# Sheet2.net
KiCad netlist of a schematic drawn in Altium Designer
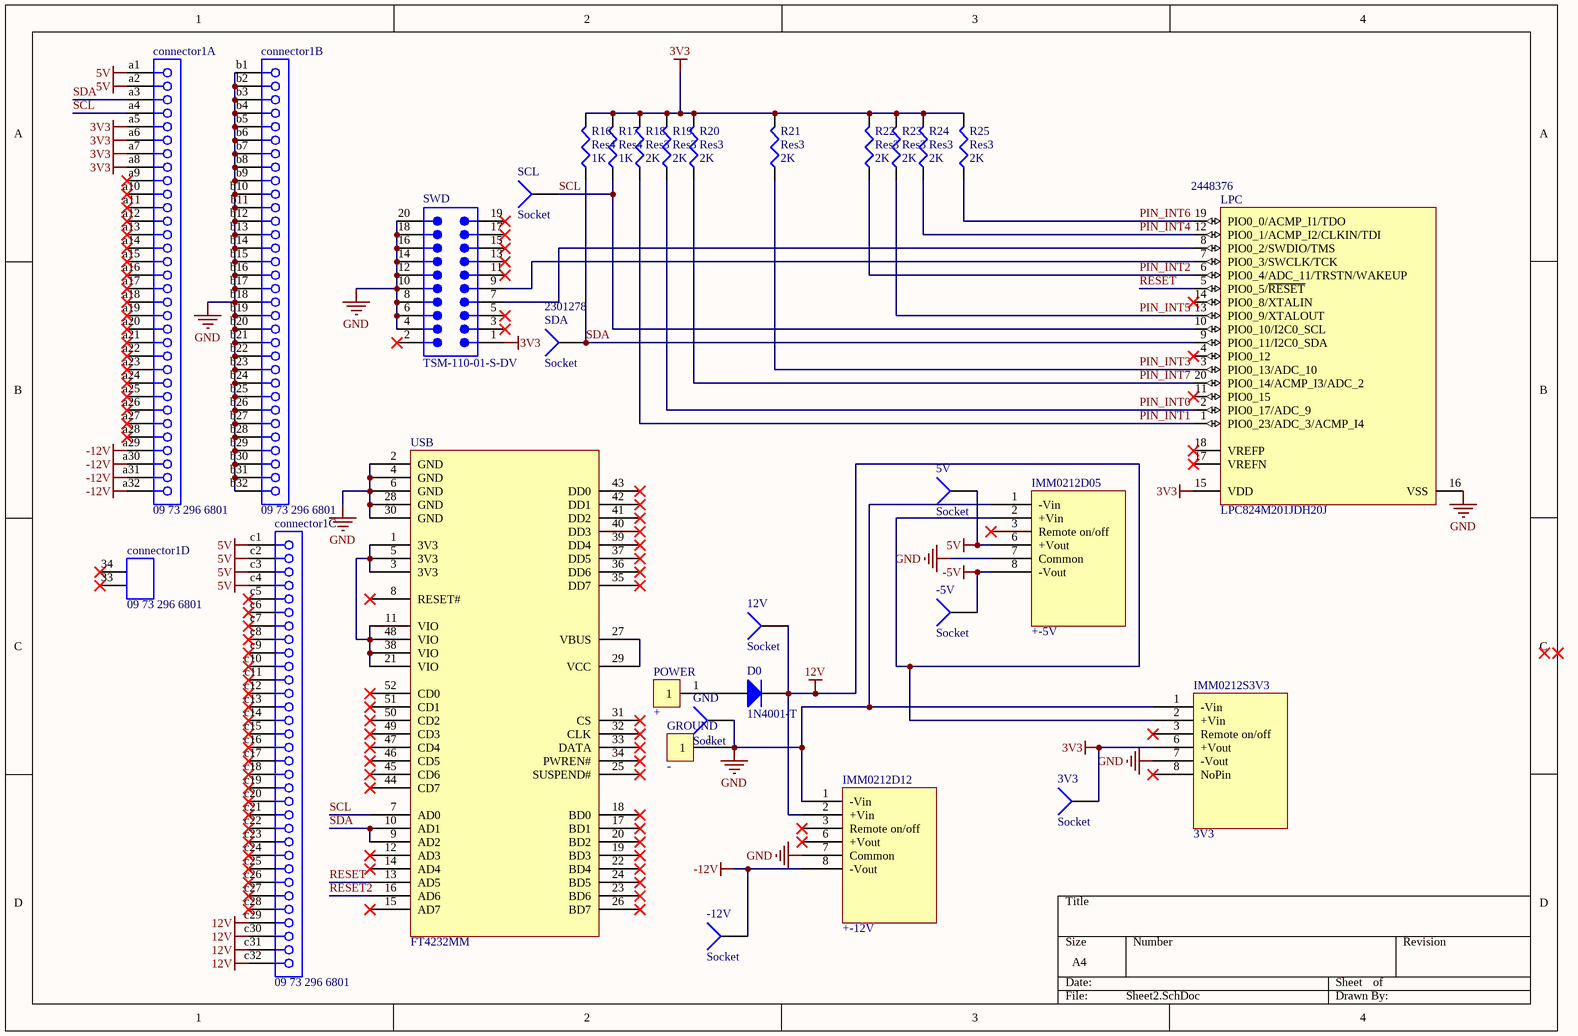
[diagram p0: Sheet2.SchDoc]

(export (version "E")
  (design (tool "Eeschema 10.0.6"))
  (components
    (comp (ref "-5V")
      (value "Socket")
      (footprint "CON1")
      (fields (field (name "PUBLISHER") "Altium Limited"))
      (libsource (lib "Miscellaneous Connectors") (part "Socket"))
    )
    (comp (ref "-12V")
      (value "Socket")
      (footprint "CON1")
      (fields (field (name "PUBLISHER") "Altium Limited"))
      (libsource (lib "Miscellaneous Connectors") (part "Socket"))
    )
    (comp (ref "3V3")
      (value "Socket")
      (footprint "CON1")
      (fields (field (name "PUBLISHER") "Altium Limited"))
      (libsource (lib "Miscellaneous Connectors") (part "Socket"))
    )
    (comp (ref "5V")
      (value "Socket")
      (footprint "CON1")
      (fields (field (name "PUBLISHER") "Altium Limited"))
      (libsource (lib "Miscellaneous Connectors") (part "Socket"))
    )
    (comp (ref "12V")
      (value "Socket")
      (footprint "CON1")
      (fields (field (name "PUBLISHER") "Altium Limited"))
      (libsource (lib "Miscellaneous Connectors") (part "Socket"))
    )
    (comp (ref "connector1")
      (value "09 73 296 6801")
      (footprint "DAC testerPCB:0973296X801")
      (fields (field (name "PUBLISHER") "Altium Limited"))
      (libsource (lib "HARTING DIN 41612 Type R") (part "09 73 296 6801"))
    )
    (comp (ref "D0")
      (value "1N4001-T")
      (footprint "DIOD-DO-41-P-2_V")
      (description "1.0 A Rectifier, 15 pF, 50 V, -65 to 150 degC, 2-Pin DO-41 Plastic, RoHS, Tape and Reel")
      (fields (field (name "MANUFACTURER") "Diodes Inc"))
      (libsource (lib "Altium Content Vault") (part "CMP-0639-00006-2"))
    )
    (comp (ref "GND")
      (value "Socket")
      (footprint "CON1")
      (fields (field (name "PUBLISHER") "Altium Limited"))
      (libsource (lib "Miscellaneous Connectors") (part "Socket"))
    )
    (comp (ref "GROUND") (value "-") (footprint "RA") (libsource (lib "schlib") (part "Power")))
    (comp (ref "IMM0212D05")
      (value "+-5V")
      (footprint "my_pcb:SIP8")
      (libsource (lib "schlib") (part "IMM0212D05"))
    )
    (comp (ref "IMM0212D12")
      (value "+-12V")
      (footprint "SIP8")
      (libsource (lib "schlib") (part "IMM0212D05"))
    )
    (comp (ref "IMM0212S3V3")
      (value "3V3")
      (footprint "my_pcb:SIP8")
      (libsource (lib "schlib") (part "Component_1"))
    )
    (comp (ref "LPC")
      (value "LPC824M201JDH20J")
      (footprint "NXP-SOT360-1_N")
      (fields
        (field (name "MANUFACTURER") "NXP Semiconductors")
        (field (name "PARTNUMBER") "LPC824M201JDH20")
        (field (name "SUPPLIER PART NUMBER 1") "2448376")
      )
      (libsource (lib "Altium Content Vault") (part "CMP-0173-00095-1"))
    )
    (comp (ref "POWER") (value "+") (footprint "RA") (libsource (lib "schlib") (part "Power")))
    (comp (ref "R16")
      (value "Res4")
      (footprint "J1-0603")
      (description "Resistor")
      (fields (field (name "ALTIUM_VALUE") "1K") (field (name "PUBLISHER") "Altium Limited"))
      (libsource (lib "Miscellaneous Devices") (part "Res3"))
    )
    (comp (ref "R17")
      (value "Res4")
      (footprint "J1-0603")
      (description "Resistor")
      (fields (field (name "ALTIUM_VALUE") "1K") (field (name "PUBLISHER") "Altium Limited"))
      (libsource (lib "Miscellaneous Devices") (part "Res3"))
    )
    (comp (ref "R18")
      (value "Res3")
      (footprint "J1-0603")
      (description "Resistor")
      (fields (field (name "ALTIUM_VALUE") "2K") (field (name "PUBLISHER") "Altium Limited"))
      (libsource (lib "Miscellaneous Devices") (part "Res3"))
    )
    (comp (ref "R19")
      (value "Res3")
      (footprint "J1-0603")
      (description "Resistor")
      (fields (field (name "ALTIUM_VALUE") "2K") (field (name "PUBLISHER") "Altium Limited"))
      (libsource (lib "Miscellaneous Devices") (part "Res3"))
    )
    (comp (ref "R20")
      (value "Res3")
      (footprint "J1-0603")
      (description "Resistor")
      (fields (field (name "ALTIUM_VALUE") "2K") (field (name "PUBLISHER") "Altium Limited"))
      (libsource (lib "Miscellaneous Devices") (part "Res3"))
    )
    (comp (ref "R21")
      (value "Res3")
      (footprint "J1-0603")
      (description "Resistor")
      (fields (field (name "ALTIUM_VALUE") "2K") (field (name "PUBLISHER") "Altium Limited"))
      (libsource (lib "Miscellaneous Devices") (part "Res3"))
    )
    (comp (ref "R22")
      (value "Res3")
      (footprint "J1-0603")
      (description "Resistor")
      (fields (field (name "ALTIUM_VALUE") "2K") (field (name "PUBLISHER") "Altium Limited"))
      (libsource (lib "Miscellaneous Devices") (part "Res3"))
    )
    (comp (ref "R23")
      (value "Res3")
      (footprint "J1-0603")
      (description "Resistor")
      (fields (field (name "ALTIUM_VALUE") "2K") (field (name "PUBLISHER") "Altium Limited"))
      (libsource (lib "Miscellaneous Devices") (part "Res3"))
    )
    (comp (ref "R24")
      (value "Res3")
      (footprint "J1-0603")
      (description "Resistor")
      (fields (field (name "ALTIUM_VALUE") "2K") (field (name "PUBLISHER") "Altium Limited"))
      (libsource (lib "Miscellaneous Devices") (part "Res3"))
    )
    (comp (ref "R25")
      (value "Res3")
      (footprint "J1-0603")
      (description "Resistor")
      (fields (field (name "ALTIUM_VALUE") "2K") (field (name "PUBLISHER") "Altium Limited"))
      (libsource (lib "Miscellaneous Devices") (part "Res3"))
    )
    (comp (ref "SCL")
      (value "Socket")
      (footprint "CON1")
      (fields (field (name "PUBLISHER") "Altium Limited"))
      (libsource (lib "Miscellaneous Connectors") (part "Socket"))
    )
    (comp (ref "SDA")
      (value "Socket")
      (footprint "CON1")
      (fields (field (name "SUPPLIER PART NUMBER 1") "2301278") (field (name "PUBLISHER") "Altium Limited"))
      (libsource (lib "Miscellaneous Connectors") (part "Socket"))
    )
    (comp (ref "SWD")
      (value "TSM-110-01-S-DV")
      (footprint "SMTC-TSM-110-01-X-DV")
      (fields (field (name "MANUFACTURER") "Samtec"))
      (libsource (lib "Altium Content Vault") (part "CMP-1024-00283-1"))
    )
    (comp (ref "USB")
      (value "FT4232MM")
      (footprint "ICfootprint3:FT4232MM")
      (description "FDTI mini module")
      (libsource (lib "nxp_device") (part "FT4232MM"))
    )
  )
  (nets
    (net (code "1") (name "-5V") (class "Default")
      (node (ref "-5V") (pin "1") (pinfunction "1_1") (pintype "passive"))
      (node (ref "IMM0212D05") (pin "8") (pinfunction "-Vout_8") (pintype "passive"))
    )
    (net (code "2") (name "-12V") (class "Default")
      (node (ref "-12V") (pin "1") (pinfunction "1_1") (pintype "passive"))
      (node (ref "IMM0212D12") (pin "8") (pinfunction "-Vout_8") (pintype "passive"))
      (node (ref "connector1") (pin "a29") (pinfunction "a29_a29") (pintype "passive"))
      (node (ref "connector1") (pin "a30") (pinfunction "a30_a30") (pintype "passive"))
      (node (ref "connector1") (pin "a31") (pinfunction "a31_a31") (pintype "passive"))
      (node (ref "connector1") (pin "a32") (pinfunction "a32_a32") (pintype "passive"))
    )
    (net (code "3") (name "/PIN_INT0") (class "Default")
      (node (ref "LPC") (pin "2") (pinfunction "PIO0_17/ADC_9_2") (pintype "bidirectional"))
      (node (ref "R19") (pin "1") (pinfunction "1_1") (pintype "passive"))
    )
    (net (code "4") (name "/PIN_INT1") (class "Default")
      (node (ref "LPC") (pin "1") (pinfunction "PIO0_23/ADC_3/ACMP_I4_1") (pintype "bidirectional"))
      (node (ref "R18") (pin "1") (pinfunction "1_1") (pintype "passive"))
    )
    (net (code "5") (name "/PIN_INT2") (class "Default")
      (node (ref "LPC") (pin "6") (pinfunction "PIO0_4/ADC_11/TRSTN/WAKEUP_6") (pintype "bidirectional"))
      (node (ref "R22") (pin "1") (pinfunction "1_1") (pintype "passive"))
    )
    (net (code "6") (name "/PIN_INT3") (class "Default")
      (node (ref "LPC") (pin "3") (pinfunction "PIO0_13/ADC_10_3") (pintype "bidirectional"))
      (node (ref "R21") (pin "1") (pinfunction "1_1") (pintype "passive"))
    )
    (net (code "7") (name "/PIN_INT4") (class "Default")
      (node (ref "LPC") (pin "12") (pinfunction "PIO0_1/ACMP_I2/CLKIN/TDI_12") (pintype "bidirectional"))
      (node (ref "R24") (pin "1") (pinfunction "1_1") (pintype "passive"))
    )
    (net (code "8") (name "/PIN_INT5") (class "Default")
      (node (ref "LPC") (pin "13") (pinfunction "PIO0_9/XTALOUT_13") (pintype "bidirectional"))
      (node (ref "R23") (pin "1") (pinfunction "1_1") (pintype "passive"))
    )
    (net (code "9") (name "/PIN_INT6") (class "Default")
      (node (ref "LPC") (pin "19") (pinfunction "PIO0_0/ACMP_I1/TDO_19") (pintype "bidirectional"))
      (node (ref "R25") (pin "1") (pinfunction "1_1") (pintype "passive"))
    )
    (net (code "10") (name "/PIN_INT7") (class "Default")
      (node (ref "LPC") (pin "20") (pinfunction "PIO0_14/ACMP_I3/ADC_2_20") (pintype "bidirectional"))
      (node (ref "R20") (pin "1") (pinfunction "1_1") (pintype "passive"))
    )
    (net (code "11") (name "/RESET") (class "Default")
      (node (ref "LPC") (pin "5") (pinfunction "PIO0_5/~{RESET}_5") (pintype "bidirectional"))
      (node (ref "USB") (pin "13") (pinfunction "AD5_13") (pintype "passive"))
    )
    (net (code "12") (name "/RESET2") (class "Default")
      (node (ref "USB") (pin "16") (pinfunction "AD6_16") (pintype "passive"))
    )
    (net (code "13") (name "/SCL") (class "Default")
      (node (ref "LPC") (pin "10") (pinfunction "PIO0_10/I2C0_SCL_10") (pintype "bidirectional"))
      (node (ref "R17") (pin "1") (pinfunction "1_1") (pintype "passive"))
      (node (ref "SCL") (pin "1") (pinfunction "1_1") (pintype "passive"))
      (node (ref "USB") (pin "7") (pinfunction "AD0_7") (pintype "passive"))
      (node (ref "connector1") (pin "a4") (pinfunction "a4_a4") (pintype "passive"))
    )
    (net (code "14") (name "/SDA") (class "Default")
      (node (ref "LPC") (pin "9") (pinfunction "PIO0_11/I2C0_SDA_9") (pintype "bidirectional"))
      (node (ref "R16") (pin "1") (pinfunction "1_1") (pintype "passive"))
      (node (ref "SDA") (pin "1") (pinfunction "1_1") (pintype "passive"))
      (node (ref "USB") (pin "10") (pinfunction "AD1_10") (pintype "passive"))
      (node (ref "USB") (pin "9") (pinfunction "AD2_9") (pintype "passive"))
      (node (ref "connector1") (pin "a3") (pinfunction "a3_a3") (pintype "passive"))
    )
    (net (code "15") (name "3V3") (class "Default")
      (node (ref "3V3") (pin "1") (pinfunction "1_1") (pintype "passive"))
      (node (ref "IMM0212S3V3") (pin "6") (pinfunction "+Vout_6") (pintype "passive"))
      (node (ref "LPC") (pin "15") (pinfunction "VDD_15") (pintype "power_in"))
      (node (ref "R16") (pin "2") (pinfunction "2_2") (pintype "passive"))
      (node (ref "R17") (pin "2") (pinfunction "2_2") (pintype "passive"))
      (node (ref "R18") (pin "2") (pinfunction "2_2") (pintype "passive"))
      (node (ref "R19") (pin "2") (pinfunction "2_2") (pintype "passive"))
      (node (ref "R20") (pin "2") (pinfunction "2_2") (pintype "passive"))
      (node (ref "R21") (pin "2") (pinfunction "2_2") (pintype "passive"))
      (node (ref "R22") (pin "2") (pinfunction "2_2") (pintype "passive"))
      (node (ref "R23") (pin "2") (pinfunction "2_2") (pintype "passive"))
      (node (ref "R24") (pin "2") (pinfunction "2_2") (pintype "passive"))
      (node (ref "R25") (pin "2") (pinfunction "2_2") (pintype "passive"))
      (node (ref "SWD") (pin "1") (pinfunction "1_1") (pintype "passive"))
      (node (ref "connector1") (pin "a5") (pinfunction "a5_a5") (pintype "passive"))
      (node (ref "connector1") (pin "a6") (pinfunction "a6_a6") (pintype "passive"))
      (node (ref "connector1") (pin "a7") (pinfunction "a7_a7") (pintype "passive"))
      (node (ref "connector1") (pin "a8") (pinfunction "a8_a8") (pintype "passive"))
    )
    (net (code "16") (name "5V") (class "Default")
      (node (ref "5V") (pin "1") (pinfunction "1_1") (pintype "passive"))
      (node (ref "IMM0212D05") (pin "6") (pinfunction "+Vout_6") (pintype "passive"))
      (node (ref "connector1") (pin "a1") (pinfunction "a1_a1") (pintype "passive"))
      (node (ref "connector1") (pin "a2") (pinfunction "a2_a2") (pintype "passive"))
      (node (ref "connector1") (pin "c1") (pinfunction "c1_c1") (pintype "passive"))
      (node (ref "connector1") (pin "c2") (pinfunction "c2_c2") (pintype "passive"))
      (node (ref "connector1") (pin "c3") (pinfunction "c3_c3") (pintype "passive"))
      (node (ref "connector1") (pin "c4") (pinfunction "c4_c4") (pintype "passive"))
    )
    (net (code "17") (name "12V") (class "Default")
      (node (ref "12V") (pin "1") (pinfunction "1_1") (pintype "passive"))
      (node (ref "D0") (pin "2") (pinfunction "K_2") (pintype "passive"))
      (node (ref "IMM0212D05") (pin "2") (pinfunction "+Vin_2") (pintype "passive"))
      (node (ref "IMM0212D12") (pin "2") (pinfunction "+Vin_2") (pintype "passive"))
      (node (ref "IMM0212S3V3") (pin "2") (pinfunction "+Vin_2") (pintype "passive"))
      (node (ref "connector1") (pin "c29") (pinfunction "c29_c29") (pintype "passive"))
      (node (ref "connector1") (pin "c30") (pinfunction "c30_c30") (pintype "passive"))
      (node (ref "connector1") (pin "c31") (pinfunction "c31_c31") (pintype "passive"))
      (node (ref "connector1") (pin "c32") (pinfunction "c32_c32") (pintype "passive"))
    )
    (net (code "18") (name "GND") (class "Default")
      (node (ref "GND") (pin "1") (pinfunction "1_1") (pintype "passive"))
      (node (ref "GROUND") (pin "1") (pinfunction "1_1") (pintype "passive"))
      (node (ref "IMM0212D05") (pin "1") (pinfunction "-Vin_1") (pintype "passive"))
      (node (ref "IMM0212D05") (pin "7") (pinfunction "Common_7") (pintype "passive"))
      (node (ref "IMM0212D12") (pin "1") (pinfunction "-Vin_1") (pintype "passive"))
      (node (ref "IMM0212D12") (pin "7") (pinfunction "Common_7") (pintype "passive"))
      (node (ref "IMM0212S3V3") (pin "1") (pinfunction "-Vin_1") (pintype "passive"))
      (node (ref "IMM0212S3V3") (pin "7") (pinfunction "-Vout_7") (pintype "passive"))
      (node (ref "LPC") (pin "16") (pinfunction "VSS_16") (pintype "power_in"))
      (node (ref "SWD") (pin "10") (pinfunction "10_10") (pintype "passive"))
      (node (ref "SWD") (pin "12") (pinfunction "12_12") (pintype "passive"))
      (node (ref "SWD") (pin "14") (pinfunction "14_14") (pintype "passive"))
      (node (ref "SWD") (pin "16") (pinfunction "16_16") (pintype "passive"))
      (node (ref "SWD") (pin "18") (pinfunction "18_18") (pintype "passive"))
      (node (ref "SWD") (pin "20") (pinfunction "20_20") (pintype "passive"))
      (node (ref "SWD") (pin "4") (pinfunction "4_4") (pintype "passive"))
      (node (ref "SWD") (pin "6") (pinfunction "6_6") (pintype "passive"))
      (node (ref "SWD") (pin "8") (pinfunction "8_8") (pintype "passive"))
      (node (ref "USB") (pin "2") (pinfunction "GND_2") (pintype "passive"))
      (node (ref "USB") (pin "28") (pinfunction "GND_28") (pintype "passive"))
      (node (ref "USB") (pin "30") (pinfunction "GND_30") (pintype "passive"))
      (node (ref "USB") (pin "4") (pinfunction "GND_4") (pintype "passive"))
      (node (ref "USB") (pin "6") (pinfunction "GND_6") (pintype "passive"))
      (node (ref "connector1") (pin "b1") (pinfunction "b1_b1") (pintype "passive"))
      (node (ref "connector1") (pin "b10") (pinfunction "b10_b10") (pintype "passive"))
      (node (ref "connector1") (pin "b11") (pinfunction "b11_b11") (pintype "passive"))
      (node (ref "connector1") (pin "b12") (pinfunction "b12_b12") (pintype "passive"))
      (node (ref "connector1") (pin "b13") (pinfunction "b13_b13") (pintype "passive"))
      (node (ref "connector1") (pin "b14") (pinfunction "b14_b14") (pintype "passive"))
      (node (ref "connector1") (pin "b15") (pinfunction "b15_b15") (pintype "passive"))
      (node (ref "connector1") (pin "b16") (pinfunction "b16_b16") (pintype "passive"))
      (node (ref "connector1") (pin "b17") (pinfunction "b17_b17") (pintype "passive"))
      (node (ref "connector1") (pin "b18") (pinfunction "b18_b18") (pintype "passive"))
      (node (ref "connector1") (pin "b19") (pinfunction "b19_b19") (pintype "passive"))
      (node (ref "connector1") (pin "b2") (pinfunction "b2_b2") (pintype "passive"))
      (node (ref "connector1") (pin "b20") (pinfunction "b20_b20") (pintype "passive"))
      (node (ref "connector1") (pin "b21") (pinfunction "b21_b21") (pintype "passive"))
      (node (ref "connector1") (pin "b22") (pinfunction "b22_b22") (pintype "passive"))
      (node (ref "connector1") (pin "b23") (pinfunction "b23_b23") (pintype "passive"))
      (node (ref "connector1") (pin "b24") (pinfunction "b24_b24") (pintype "passive"))
      (node (ref "connector1") (pin "b25") (pinfunction "b25_b25") (pintype "passive"))
      (node (ref "connector1") (pin "b26") (pinfunction "b26_b26") (pintype "passive"))
      (node (ref "connector1") (pin "b27") (pinfunction "b27_b27") (pintype "passive"))
      (node (ref "connector1") (pin "b28") (pinfunction "b28_b28") (pintype "passive"))
      (node (ref "connector1") (pin "b29") (pinfunction "b29_b29") (pintype "passive"))
      (node (ref "connector1") (pin "b3") (pinfunction "b3_b3") (pintype "passive"))
      (node (ref "connector1") (pin "b30") (pinfunction "b30_b30") (pintype "passive"))
      (node (ref "connector1") (pin "b31") (pinfunction "b31_b31") (pintype "passive"))
      (node (ref "connector1") (pin "b32") (pinfunction "b32_b32") (pintype "passive"))
      (node (ref "connector1") (pin "b4") (pinfunction "b4_b4") (pintype "passive"))
      (node (ref "connector1") (pin "b5") (pinfunction "b5_b5") (pintype "passive"))
      (node (ref "connector1") (pin "b6") (pinfunction "b6_b6") (pintype "passive"))
      (node (ref "connector1") (pin "b7") (pinfunction "b7_b7") (pintype "passive"))
      (node (ref "connector1") (pin "b8") (pinfunction "b8_b8") (pintype "passive"))
      (node (ref "connector1") (pin "b9") (pinfunction "b9_b9") (pintype "passive"))
    )
    (net (code "19") (name "Net-(D0-A)") (class "Default")
      (node (ref "D0") (pin "1") (pinfunction "A_1") (pintype "passive"))
      (node (ref "POWER") (pin "1") (pinfunction "1_1") (pintype "passive"))
    )
    (net (code "20") (name "Net-(LPC-PIO0_2{slash}SWDIO{slash}TMS)") (class "Default")
      (node (ref "LPC") (pin "8") (pinfunction "PIO0_2/SWDIO/TMS_8") (pintype "bidirectional"))
      (node (ref "SWD") (pin "7") (pinfunction "7_7") (pintype "passive"))
    )
    (net (code "21") (name "Net-(LPC-PIO0_3{slash}SWCLK{slash}TCK)") (class "Default")
      (node (ref "LPC") (pin "7") (pinfunction "PIO0_3/SWCLK/TCK_7") (pintype "bidirectional"))
      (node (ref "SWD") (pin "9") (pinfunction "9_9") (pintype "passive"))
    )
    (net (code "22") (name "Net-(USB-3V3-Pad1)") (class "Default")
      (node (ref "USB") (pin "1") (pinfunction "3V3_1") (pintype "passive"))
      (node (ref "USB") (pin "11") (pinfunction "VIO_11") (pintype "passive"))
      (node (ref "USB") (pin "21") (pinfunction "VIO_21") (pintype "passive"))
      (node (ref "USB") (pin "3") (pinfunction "3V3_3") (pintype "passive"))
      (node (ref "USB") (pin "38") (pinfunction "VIO_38") (pintype "passive"))
      (node (ref "USB") (pin "48") (pinfunction "VIO_48") (pintype "passive"))
      (node (ref "USB") (pin "5") (pinfunction "3V3_5") (pintype "passive"))
    )
    (net (code "23") (name "Net-(USB-VBUS)") (class "Default")
      (node (ref "USB") (pin "27") (pinfunction "VBUS_27") (pintype "passive"))
      (node (ref "USB") (pin "29") (pinfunction "VCC_29") (pintype "passive"))
    )
    (net (code "24") (name "unconnected-(IMM0212D05-Remote_on{slash}off-Pad3)") (class "Default")
      (node (ref "IMM0212D05") (pin "3") (pinfunction "Remote_on/off_3") (pintype "passive+no_connect"))
    )
    (net (code "25") (name "unconnected-(IMM0212D12-+Vout-Pad6)") (class "Default")
      (node (ref "IMM0212D12") (pin "6") (pinfunction "+Vout_6") (pintype "passive+no_connect"))
    )
    (net (code "26") (name "unconnected-(IMM0212D12-Remote_on{slash}off-Pad3)") (class "Default")
      (node (ref "IMM0212D12") (pin "3") (pinfunction "Remote_on/off_3") (pintype "passive+no_connect"))
    )
    (net (code "27") (name "unconnected-(IMM0212S3V3-NoPin-Pad8)") (class "Default")
      (node (ref "IMM0212S3V3") (pin "8") (pinfunction "NoPin_8") (pintype "passive+no_connect"))
    )
    (net (code "28") (name "unconnected-(IMM0212S3V3-Remote_on{slash}off-Pad3)") (class "Default")
      (node (ref "IMM0212S3V3") (pin "3") (pinfunction "Remote_on/off_3") (pintype "passive+no_connect"))
    )
    (net (code "29") (name "unconnected-(LPC-PIO0_8{slash}XTALIN-Pad14)") (class "Default")
      (node (ref "LPC") (pin "14") (pinfunction "PIO0_8/XTALIN_14") (pintype "bidirectional+no_connect"))
    )
    (net (code "30") (name "unconnected-(LPC-PIO0_12-Pad4)") (class "Default")
      (node (ref "LPC") (pin "4") (pinfunction "PIO0_12_4") (pintype "bidirectional+no_connect"))
    )
    (net (code "31") (name "unconnected-(LPC-PIO0_15-Pad11)") (class "Default")
      (node (ref "LPC") (pin "11") (pinfunction "PIO0_15_11") (pintype "bidirectional+no_connect"))
    )
    (net (code "32") (name "unconnected-(LPC-VREFN-Pad17)") (class "Default")
      (node (ref "LPC") (pin "17") (pinfunction "VREFN_17") (pintype "power_in+no_connect"))
    )
    (net (code "33") (name "unconnected-(LPC-VREFP-Pad18)") (class "Default")
      (node (ref "LPC") (pin "18") (pinfunction "VREFP_18") (pintype "power_in+no_connect"))
    )
    (net (code "34") (name "unconnected-(SWD-Pad2)") (class "Default")
      (node (ref "SWD") (pin "2") (pinfunction "2_2") (pintype "passive+no_connect"))
    )
    (net (code "35") (name "unconnected-(SWD-Pad3)") (class "Default")
      (node (ref "SWD") (pin "3") (pinfunction "3_3") (pintype "passive+no_connect"))
    )
    (net (code "36") (name "unconnected-(SWD-Pad5)") (class "Default")
      (node (ref "SWD") (pin "5") (pinfunction "5_5") (pintype "passive+no_connect"))
    )
    (net (code "37") (name "unconnected-(SWD-Pad11)") (class "Default")
      (node (ref "SWD") (pin "11") (pinfunction "11_11") (pintype "passive+no_connect"))
    )
    (net (code "38") (name "unconnected-(SWD-Pad13)") (class "Default")
      (node (ref "SWD") (pin "13") (pinfunction "13_13") (pintype "passive+no_connect"))
    )
    (net (code "39") (name "unconnected-(SWD-Pad15)") (class "Default")
      (node (ref "SWD") (pin "15") (pinfunction "15_15") (pintype "passive+no_connect"))
    )
    (net (code "40") (name "unconnected-(SWD-Pad17)") (class "Default")
      (node (ref "SWD") (pin "17") (pinfunction "17_17") (pintype "passive+no_connect"))
    )
    (net (code "41") (name "unconnected-(SWD-Pad19)") (class "Default")
      (node (ref "SWD") (pin "19") (pinfunction "19_19") (pintype "passive+no_connect"))
    )
    (net (code "42") (name "unconnected-(USB-AD3-Pad12)") (class "Default")
      (node (ref "USB") (pin "12") (pinfunction "AD3_12") (pintype "passive+no_connect"))
    )
    (net (code "43") (name "unconnected-(USB-AD4-Pad14)") (class "Default")
      (node (ref "USB") (pin "14") (pinfunction "AD4_14") (pintype "passive+no_connect"))
    )
    (net (code "44") (name "unconnected-(USB-AD7-Pad15)") (class "Default")
      (node (ref "USB") (pin "15") (pinfunction "AD7_15") (pintype "passive+no_connect"))
    )
    (net (code "45") (name "unconnected-(USB-BD0-Pad18)") (class "Default")
      (node (ref "USB") (pin "18") (pinfunction "BD0_18") (pintype "passive+no_connect"))
    )
    (net (code "46") (name "unconnected-(USB-BD1-Pad17)") (class "Default")
      (node (ref "USB") (pin "17") (pinfunction "BD1_17") (pintype "passive+no_connect"))
    )
    (net (code "47") (name "unconnected-(USB-BD2-Pad20)") (class "Default")
      (node (ref "USB") (pin "20") (pinfunction "BD2_20") (pintype "passive+no_connect"))
    )
    (net (code "48") (name "unconnected-(USB-BD3-Pad19)") (class "Default")
      (node (ref "USB") (pin "19") (pinfunction "BD3_19") (pintype "passive+no_connect"))
    )
    (net (code "49") (name "unconnected-(USB-BD4-Pad22)") (class "Default")
      (node (ref "USB") (pin "22") (pinfunction "BD4_22") (pintype "passive+no_connect"))
    )
    (net (code "50") (name "unconnected-(USB-BD5-Pad24)") (class "Default")
      (node (ref "USB") (pin "24") (pinfunction "BD5_24") (pintype "passive+no_connect"))
    )
    (net (code "51") (name "unconnected-(USB-BD6-Pad23)") (class "Default")
      (node (ref "USB") (pin "23") (pinfunction "BD6_23") (pintype "passive+no_connect"))
    )
    (net (code "52") (name "unconnected-(USB-BD7-Pad26)") (class "Default")
      (node (ref "USB") (pin "26") (pinfunction "BD7_26") (pintype "passive+no_connect"))
    )
    (net (code "53") (name "unconnected-(USB-CD0-Pad52)") (class "Default")
      (node (ref "USB") (pin "52") (pinfunction "CD0_52") (pintype "passive+no_connect"))
    )
    (net (code "54") (name "unconnected-(USB-CD1-Pad51)") (class "Default")
      (node (ref "USB") (pin "51") (pinfunction "CD1_51") (pintype "passive+no_connect"))
    )
    (net (code "55") (name "unconnected-(USB-CD2-Pad50)") (class "Default")
      (node (ref "USB") (pin "50") (pinfunction "CD2_50") (pintype "passive+no_connect"))
    )
    (net (code "56") (name "unconnected-(USB-CD3-Pad49)") (class "Default")
      (node (ref "USB") (pin "49") (pinfunction "CD3_49") (pintype "passive+no_connect"))
    )
    (net (code "57") (name "unconnected-(USB-CD4-Pad47)") (class "Default")
      (node (ref "USB") (pin "47") (pinfunction "CD4_47") (pintype "passive+no_connect"))
    )
    (net (code "58") (name "unconnected-(USB-CD5-Pad46)") (class "Default")
      (node (ref "USB") (pin "46") (pinfunction "CD5_46") (pintype "passive+no_connect"))
    )
    (net (code "59") (name "unconnected-(USB-CD6-Pad45)") (class "Default")
      (node (ref "USB") (pin "45") (pinfunction "CD6_45") (pintype "passive+no_connect"))
    )
    (net (code "60") (name "unconnected-(USB-CD7-Pad44)") (class "Default")
      (node (ref "USB") (pin "44") (pinfunction "CD7_44") (pintype "passive+no_connect"))
    )
    (net (code "61") (name "unconnected-(USB-CLK-Pad32)") (class "Default")
      (node (ref "USB") (pin "32") (pinfunction "CLK_32") (pintype "passive+no_connect"))
    )
    (net (code "62") (name "unconnected-(USB-CS-Pad31)") (class "Default")
      (node (ref "USB") (pin "31") (pinfunction "CS_31") (pintype "passive+no_connect"))
    )
    (net (code "63") (name "unconnected-(USB-DATA-Pad33)") (class "Default")
      (node (ref "USB") (pin "33") (pinfunction "DATA_33") (pintype "passive+no_connect"))
    )
    (net (code "64") (name "unconnected-(USB-DD0-Pad43)") (class "Default")
      (node (ref "USB") (pin "43") (pinfunction "DD0_43") (pintype "passive+no_connect"))
    )
    (net (code "65") (name "unconnected-(USB-DD1-Pad42)") (class "Default")
      (node (ref "USB") (pin "42") (pinfunction "DD1_42") (pintype "passive+no_connect"))
    )
    (net (code "66") (name "unconnected-(USB-DD2-Pad41)") (class "Default")
      (node (ref "USB") (pin "41") (pinfunction "DD2_41") (pintype "passive+no_connect"))
    )
    (net (code "67") (name "unconnected-(USB-DD3-Pad40)") (class "Default")
      (node (ref "USB") (pin "40") (pinfunction "DD3_40") (pintype "passive+no_connect"))
    )
    (net (code "68") (name "unconnected-(USB-DD4-Pad39)") (class "Default")
      (node (ref "USB") (pin "39") (pinfunction "DD4_39") (pintype "passive+no_connect"))
    )
    (net (code "69") (name "unconnected-(USB-DD5-Pad37)") (class "Default")
      (node (ref "USB") (pin "37") (pinfunction "DD5_37") (pintype "passive+no_connect"))
    )
    (net (code "70") (name "unconnected-(USB-DD6-Pad36)") (class "Default")
      (node (ref "USB") (pin "36") (pinfunction "DD6_36") (pintype "passive+no_connect"))
    )
    (net (code "71") (name "unconnected-(USB-DD7-Pad35)") (class "Default")
      (node (ref "USB") (pin "35") (pinfunction "DD7_35") (pintype "passive+no_connect"))
    )
    (net (code "72") (name "unconnected-(USB-PWREN#-Pad34)") (class "Default")
      (node (ref "USB") (pin "34") (pinfunction "PWREN#_34") (pintype "passive+no_connect"))
    )
    (net (code "73") (name "unconnected-(USB-RESET#-Pad8)") (class "Default")
      (node (ref "USB") (pin "8") (pinfunction "RESET#_8") (pintype "passive+no_connect"))
    )
    (net (code "74") (name "unconnected-(USB-SUSPEND#-Pad25)") (class "Default")
      (node (ref "USB") (pin "25") (pinfunction "SUSPEND#_25") (pintype "passive+no_connect"))
    )
    (net (code "75") (name "unconnected-(connector1-Pada9)") (class "Default")
      (node (ref "connector1") (pin "a9") (pinfunction "a9_a9") (pintype "passive+no_connect"))
    )
    (net (code "76") (name "unconnected-(connector1-Pada10)") (class "Default")
      (node (ref "connector1") (pin "a10") (pinfunction "a10_a10") (pintype "passive+no_connect"))
    )
    (net (code "77") (name "unconnected-(connector1-Pada11)") (class "Default")
      (node (ref "connector1") (pin "a11") (pinfunction "a11_a11") (pintype "passive+no_connect"))
    )
    (net (code "78") (name "unconnected-(connector1-Pada12)") (class "Default")
      (node (ref "connector1") (pin "a12") (pinfunction "a12_a12") (pintype "passive+no_connect"))
    )
    (net (code "79") (name "unconnected-(connector1-Pada13)") (class "Default")
      (node (ref "connector1") (pin "a13") (pinfunction "a13_a13") (pintype "passive+no_connect"))
    )
    (net (code "80") (name "unconnected-(connector1-Pada14)") (class "Default")
      (node (ref "connector1") (pin "a14") (pinfunction "a14_a14") (pintype "passive+no_connect"))
    )
    (net (code "81") (name "unconnected-(connector1-Pada15)") (class "Default")
      (node (ref "connector1") (pin "a15") (pinfunction "a15_a15") (pintype "passive+no_connect"))
    )
    (net (code "82") (name "unconnected-(connector1-Pada16)") (class "Default")
      (node (ref "connector1") (pin "a16") (pinfunction "a16_a16") (pintype "passive+no_connect"))
    )
    (net (code "83") (name "unconnected-(connector1-Pada17)") (class "Default")
      (node (ref "connector1") (pin "a17") (pinfunction "a17_a17") (pintype "passive+no_connect"))
    )
    (net (code "84") (name "unconnected-(connector1-Pada18)") (class "Default")
      (node (ref "connector1") (pin "a18") (pinfunction "a18_a18") (pintype "passive+no_connect"))
    )
    (net (code "85") (name "unconnected-(connector1-Pada19)") (class "Default")
      (node (ref "connector1") (pin "a19") (pinfunction "a19_a19") (pintype "passive+no_connect"))
    )
    (net (code "86") (name "unconnected-(connector1-Pada20)") (class "Default")
      (node (ref "connector1") (pin "a20") (pinfunction "a20_a20") (pintype "passive+no_connect"))
    )
    (net (code "87") (name "unconnected-(connector1-Pada21)") (class "Default")
      (node (ref "connector1") (pin "a21") (pinfunction "a21_a21") (pintype "passive+no_connect"))
    )
    (net (code "88") (name "unconnected-(connector1-Pada22)") (class "Default")
      (node (ref "connector1") (pin "a22") (pinfunction "a22_a22") (pintype "passive+no_connect"))
    )
    (net (code "89") (name "unconnected-(connector1-Pada23)") (class "Default")
      (node (ref "connector1") (pin "a23") (pinfunction "a23_a23") (pintype "passive+no_connect"))
    )
    (net (code "90") (name "unconnected-(connector1-Pada24)") (class "Default")
      (node (ref "connector1") (pin "a24") (pinfunction "a24_a24") (pintype "passive+no_connect"))
    )
    (net (code "91") (name "unconnected-(connector1-Pada25)") (class "Default")
      (node (ref "connector1") (pin "a25") (pinfunction "a25_a25") (pintype "passive+no_connect"))
    )
    (net (code "92") (name "unconnected-(connector1-Pada26)") (class "Default")
      (node (ref "connector1") (pin "a26") (pinfunction "a26_a26") (pintype "passive+no_connect"))
    )
    (net (code "93") (name "unconnected-(connector1-Pada27)") (class "Default")
      (node (ref "connector1") (pin "a27") (pinfunction "a27_a27") (pintype "passive+no_connect"))
    )
    (net (code "94") (name "unconnected-(connector1-Pada28)") (class "Default")
      (node (ref "connector1") (pin "a28") (pinfunction "a28_a28") (pintype "passive+no_connect"))
    )
    (net (code "95") (name "unconnected-(connector1-Padc5)") (class "Default")
      (node (ref "connector1") (pin "c5") (pinfunction "c5_c5") (pintype "passive+no_connect"))
    )
    (net (code "96") (name "unconnected-(connector1-Padc6)") (class "Default")
      (node (ref "connector1") (pin "c6") (pinfunction "c6_c6") (pintype "passive+no_connect"))
    )
    (net (code "97") (name "unconnected-(connector1-Padc7)") (class "Default")
      (node (ref "connector1") (pin "c7") (pinfunction "c7_c7") (pintype "passive+no_connect"))
    )
    (net (code "98") (name "unconnected-(connector1-Padc8)") (class "Default")
      (node (ref "connector1") (pin "c8") (pinfunction "c8_c8") (pintype "passive+no_connect"))
    )
    (net (code "99") (name "unconnected-(connector1-Padc9)") (class "Default")
      (node (ref "connector1") (pin "c9") (pinfunction "c9_c9") (pintype "passive+no_connect"))
    )
    (net (code "100") (name "unconnected-(connector1-Padc10)") (class "Default")
      (node (ref "connector1") (pin "c10") (pinfunction "c10_c10") (pintype "passive+no_connect"))
    )
    (net (code "101") (name "unconnected-(connector1-Padc11)") (class "Default")
      (node (ref "connector1") (pin "c11") (pinfunction "c11_c11") (pintype "passive+no_connect"))
    )
    (net (code "102") (name "unconnected-(connector1-Padc12)") (class "Default")
      (node (ref "connector1") (pin "c12") (pinfunction "c12_c12") (pintype "passive+no_connect"))
    )
    (net (code "103") (name "unconnected-(connector1-Padc13)") (class "Default")
      (node (ref "connector1") (pin "c13") (pinfunction "c13_c13") (pintype "passive+no_connect"))
    )
    (net (code "104") (name "unconnected-(connector1-Padc14)") (class "Default")
      (node (ref "connector1") (pin "c14") (pinfunction "c14_c14") (pintype "passive+no_connect"))
    )
    (net (code "105") (name "unconnected-(connector1-Padc15)") (class "Default")
      (node (ref "connector1") (pin "c15") (pinfunction "c15_c15") (pintype "passive+no_connect"))
    )
    (net (code "106") (name "unconnected-(connector1-Padc16)") (class "Default")
      (node (ref "connector1") (pin "c16") (pinfunction "c16_c16") (pintype "passive+no_connect"))
    )
    (net (code "107") (name "unconnected-(connector1-Padc17)") (class "Default")
      (node (ref "connector1") (pin "c17") (pinfunction "c17_c17") (pintype "passive+no_connect"))
    )
    (net (code "108") (name "unconnected-(connector1-Padc18)") (class "Default")
      (node (ref "connector1") (pin "c18") (pinfunction "c18_c18") (pintype "passive+no_connect"))
    )
    (net (code "109") (name "unconnected-(connector1-Padc19)") (class "Default")
      (node (ref "connector1") (pin "c19") (pinfunction "c19_c19") (pintype "passive+no_connect"))
    )
    (net (code "110") (name "unconnected-(connector1-Padc20)") (class "Default")
      (node (ref "connector1") (pin "c20") (pinfunction "c20_c20") (pintype "passive+no_connect"))
    )
    (net (code "111") (name "unconnected-(connector1-Padc21)") (class "Default")
      (node (ref "connector1") (pin "c21") (pinfunction "c21_c21") (pintype "passive+no_connect"))
    )
    (net (code "112") (name "unconnected-(connector1-Padc22)") (class "Default")
      (node (ref "connector1") (pin "c22") (pinfunction "c22_c22") (pintype "passive+no_connect"))
    )
    (net (code "113") (name "unconnected-(connector1-Padc23)") (class "Default")
      (node (ref "connector1") (pin "c23") (pinfunction "c23_c23") (pintype "passive+no_connect"))
    )
    (net (code "114") (name "unconnected-(connector1-Padc24)") (class "Default")
      (node (ref "connector1") (pin "c24") (pinfunction "c24_c24") (pintype "passive+no_connect"))
    )
    (net (code "115") (name "unconnected-(connector1-Padc25)") (class "Default")
      (node (ref "connector1") (pin "c25") (pinfunction "c25_c25") (pintype "passive+no_connect"))
    )
    (net (code "116") (name "unconnected-(connector1-Padc26)") (class "Default")
      (node (ref "connector1") (pin "c26") (pinfunction "c26_c26") (pintype "passive+no_connect"))
    )
    (net (code "117") (name "unconnected-(connector1-Padc27)") (class "Default")
      (node (ref "connector1") (pin "c27") (pinfunction "c27_c27") (pintype "passive+no_connect"))
    )
    (net (code "118") (name "unconnected-(connector1-Padc28)") (class "Default")
      (node (ref "connector1") (pin "c28") (pinfunction "c28_c28") (pintype "passive+no_connect"))
    )
    (net (code "119") (name "unconnected-(connector1D-MH1-Pad33)") (class "Default")
      (node (ref "connector1") (pin "33") (pinfunction "MH1_33") (pintype "passive+no_connect"))
    )
    (net (code "120") (name "unconnected-(connector1D-MH2-Pad34)") (class "Default")
      (node (ref "connector1") (pin "34") (pinfunction "MH2_34") (pintype "passive+no_connect"))
    )
  )
)
